# NTC.net
KiCad netlist of a schematic drawn in EAGLE
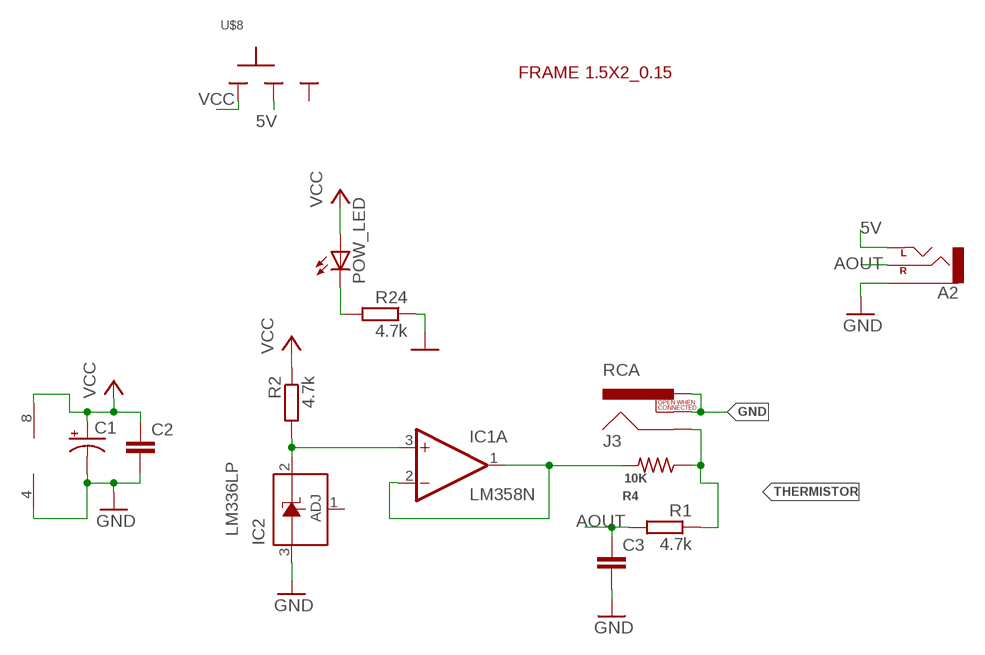
[diagram p0: schematic, sheet 1]

(export (version "E")
  (design (tool "Eeschema 10.0.6"))
  (components
    (comp (ref "A2")
      (value "AUX-CONNECTOR_CEDT_JANUARY_2015_V5_AUDIO-JACKPTH")
      (footprint "eagle-import:AUX-CONNECTOR_CEDT_JANUARY_2015_V5_AUDIO-JACK")
      (libsource (lib "eagle-import") (part "AUX-CONNECTOR_CEDT_JANUARY_2015_V5_AUDIO-JACKPTH"))
    )
    (comp (ref "C1")
      (value "CAP_POL")
      (footprint "eagle-import:E2,5-5-10U")
      (libsource (lib "eagle-import") (part "CAP_POL"))
    )
    (comp (ref "C2")
      (value "C-EU025-024X044")
      (footprint "eagle-import:C025-024X044")
      (libsource (lib "eagle-import") (part "C-EU025-024X044"))
    )
    (comp (ref "C3")
      (value "C-EU025-024X044")
      (footprint "eagle-import:C025-024X044")
      (libsource (lib "eagle-import") (part "C-EU025-024X044"))
    )
    (comp (ref "IC1")
      (value "LM358N")
      (footprint "eagle-import:DIL08")
      (libsource (lib "eagle-import") (part "LM358N"))
    )
    (comp (ref "IC2")
      (value "LM336LP")
      (footprint "eagle-import:TO92")
      (libsource (lib "eagle-import") (part "LM336LP"))
    )
    (comp (ref "J3")
      (value "RCA")
      (footprint "eagle-import:RCA")
      (libsource (lib "eagle-import") (part "RCA"))
    )
    (comp (ref "POW_LED")
      (value "LED3MM")
      (footprint "eagle-import:LED3MM")
      (libsource (lib "eagle-import") (part "LED3MM"))
    )
    (comp (ref "R1")
      (value "4.7k")
      (footprint "eagle-import:0204_7")
      (libsource (lib "eagle-import") (part "R-EU_0204/7"))
    )
    (comp (ref "R2")
      (value "4.7k")
      (footprint "eagle-import:0204_7")
      (libsource (lib "eagle-import") (part "R-EU_0204/7"))
    )
    (comp (ref "R4")
      (value "10K")
      (footprint "eagle-import:0204_7")
      (libsource (lib "eagle-import") (part "R-US_0204/7"))
    )
    (comp (ref "R24")
      (value "4.7k")
      (footprint "eagle-import:0204_7")
      (libsource (lib "eagle-import") (part "R-EU_0204/7"))
    )
    (comp (ref "U$1")
      (value "FRAME_1.5X2_RAD_0.15")
      (footprint "eagle-import:FRAME_1.5X2_RAD_0.15")
      (libsource (lib "eagle-import") (part "FRAME_1.5X2_RAD_0.15"))
    )
    (comp (ref "U$8")
      (value "SLIDESWITCH-BIG")
      (footprint "eagle-import:BIGSWITCH")
      (libsource (lib "eagle-import") (part "SLIDESWITCH-BIG"))
    )
  )
  (nets
    (net (code "1") (name "/5V") (class "Default")
      (node (ref "A2") (pin "TIP") (pinfunction "LEFT_TIP") (pintype "bidirectional"))
      (node (ref "U$8") (pin "2") (pinfunction "2_2") (pintype "bidirectional"))
    )
    (net (code "2") (name "/AOUT") (class "Default")
      (node (ref "A2") (pin "RING") (pinfunction "RIGHT_RING") (pintype "bidirectional"))
      (node (ref "C3") (pin "1") (pinfunction "1_1") (pintype "passive"))
      (node (ref "R1") (pin "2") (pinfunction "2_2") (pintype "passive"))
    )
    (net (code "3") (name "GND") (class "Default")
      (node (ref "A2") (pin "SLEEVE") (pinfunction "SLEEVE_SLEEVE") (pintype "bidirectional"))
      (node (ref "C1") (pin "-") (pinfunction "-_-") (pintype "passive"))
      (node (ref "C2") (pin "2") (pinfunction "2_2") (pintype "passive"))
      (node (ref "C3") (pin "2") (pinfunction "2_2") (pintype "passive"))
      (node (ref "IC1") (pin "4") (pinfunction "V-_4") (pintype "power_in"))
      (node (ref "IC2") (pin "3") (pinfunction "A_3") (pintype "input"))
      (node (ref "J3") (pin "PIN") (pinfunction "PIN_PIN") (pintype "bidirectional"))
      (node (ref "J3") (pin "SWITCH") (pinfunction "SWITCH_SWITCH") (pintype "bidirectional"))
      (node (ref "R24") (pin "1") (pinfunction "1_1") (pintype "passive"))
    )
    (net (code "4") (name "Net-(IC1A-+IN)") (class "Default")
      (node (ref "IC1") (pin "3") (pinfunction "+IN_3") (pintype "input"))
      (node (ref "IC2") (pin "2") (pinfunction "C_2") (pintype "passive"))
      (node (ref "R2") (pin "2") (pinfunction "2_2") (pintype "passive"))
    )
    (net (code "5") (name "Net-(IC1A--IN)") (class "Default")
      (node (ref "IC1") (pin "1") (pinfunction "OUT_1") (pintype "output"))
      (node (ref "IC1") (pin "2") (pinfunction "-IN_2") (pintype "input"))
      (node (ref "R4") (pin "2") (pinfunction "2_2") (pintype "passive"))
    )
    (net (code "6") (name "Net-(POW_LED-C)") (class "Default")
      (node (ref "POW_LED") (pin "K") (pinfunction "C_K") (pintype "passive"))
      (node (ref "R24") (pin "2") (pinfunction "2_2") (pintype "passive"))
    )
    (net (code "7") (name "THERMISTOR") (class "Default")
      (node (ref "J3") (pin "SHELL") (pinfunction "SHELL_SHELL") (pintype "bidirectional"))
      (node (ref "R1") (pin "1") (pinfunction "1_1") (pintype "passive"))
      (node (ref "R4") (pin "1") (pinfunction "1_1") (pintype "passive"))
    )
    (net (code "8") (name "VCC") (class "Default")
      (node (ref "C1") (pin "+") (pinfunction "+_+") (pintype "passive"))
      (node (ref "C2") (pin "1") (pinfunction "1_1") (pintype "passive"))
      (node (ref "IC1") (pin "8") (pinfunction "V+_8") (pintype "power_in"))
      (node (ref "POW_LED") (pin "A") (pinfunction "A_A") (pintype "passive"))
      (node (ref "R2") (pin "1") (pinfunction "1_1") (pintype "passive"))
      (node (ref "U$8") (pin "1") (pinfunction "1_1") (pintype "bidirectional"))
    )
    (net (code "9") (name "unconnected-(IC2-ADJ-Pad1)") (class "Default")
      (node (ref "IC2") (pin "1") (pinfunction "ADJ_1") (pintype "input"))
    )
    (net (code "10") (name "unconnected-(U$8-Pad3)") (class "Default")
      (node (ref "U$8") (pin "3") (pinfunction "3_3") (pintype "bidirectional"))
    )
  )
)
